# POWER.net
KiCad netlist of a schematic drawn in Altium Designer
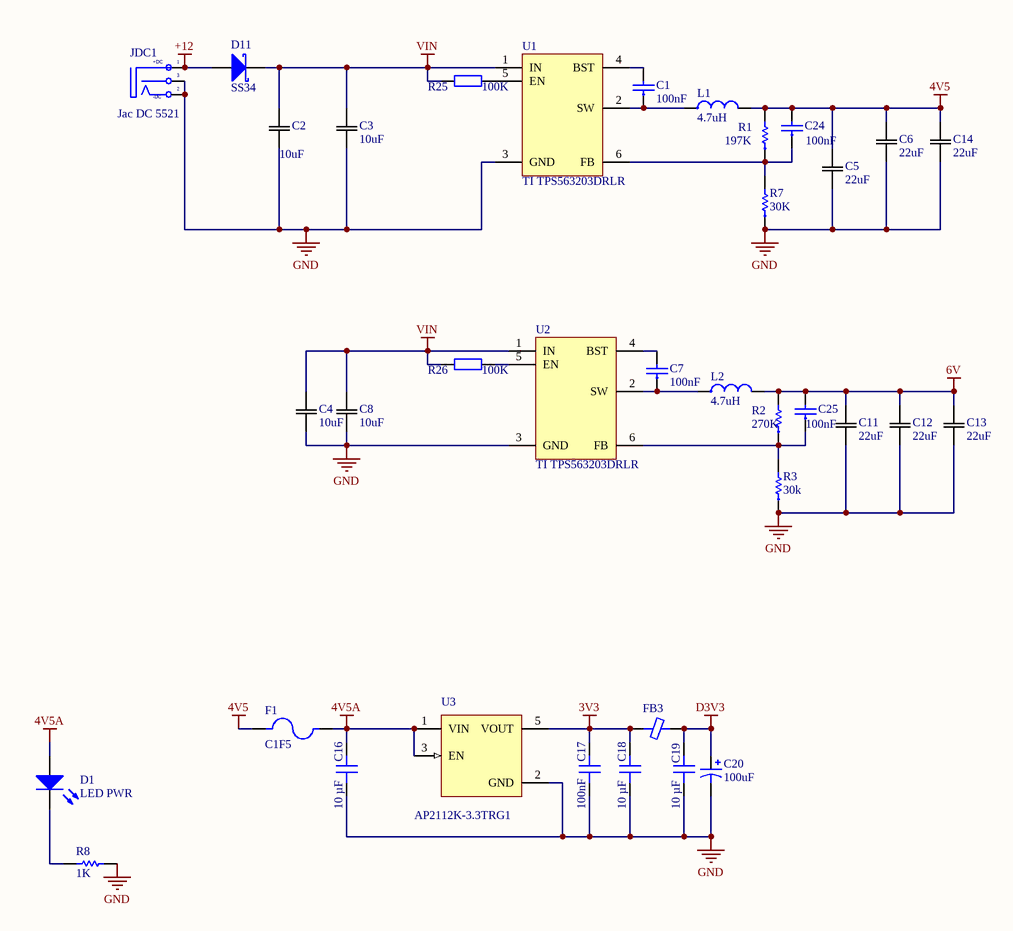
[diagram p0: POWER.SchDoc]

(export (version "E")
  (design (tool "Eeschema 10.0.6"))
  (components
    (comp (ref "C1")
      (value "100nF")
      (footprint "C0603")
      (description "CAP CER 100nF 10% 50V X7R 0603 SMD")
      (libsource (lib "2502-GMQLITE-MAIN") (part "CAPCER0001 100nF 10% 50V X7R 0603 SMD_1"))
    )
    (comp (ref "C2")
      (value "10uF")
      (footprint "CAP_CL10_SAM")
      (description "Description")
      (fields
        (field (name "MANUFACTURER_PART_NUMBER") "CL10A106MQ8NNNC")
        (field (name "COPYRIGHT") "Copyright (C) 2026 Ultra Librarian. All rights reserved.")
      )
      (libsource (lib "CL10A106MQ8NNNC") (part "CL10A106MQ8NNNC"))
    )
    (comp (ref "C3")
      (value "10uF")
      (footprint "CAP_CL10_SAM")
      (description "Description")
      (fields
        (field (name "MANUFACTURER_PART_NUMBER") "CL10A106MQ8NNNC")
        (field (name "COPYRIGHT") "Copyright (C) 2026 Ultra Librarian. All rights reserved.")
      )
      (libsource (lib "CL10A106MQ8NNNC") (part "CL10A106MQ8NNNC"))
    )
    (comp (ref "C4")
      (value "10uF")
      (footprint "CAP_CL10_SAM")
      (description "Description")
      (fields
        (field (name "MANUFACTURER_PART_NUMBER") "CL10A106MQ8NNNC")
        (field (name "COPYRIGHT") "Copyright (C) 2026 Ultra Librarian. All rights reserved.")
      )
      (libsource (lib "CL10A106MQ8NNNC") (part "CL10A106MQ8NNNC"))
    )
    (comp (ref "C5")
      (value "22uF")
      (footprint "G-188_MUR")
      (description "Description")
      (fields
        (field (name "MANUFACTURER_PART_NUMBER") "GRM188R60J226MEA0D")
        (field (name "COPYRIGHT") "Copyright (C) 2026 Ultra Librarian. All rights reserved.")
      )
      (libsource (lib "GRM188R60J226MEA0D") (part "GRM188R60J226MEA0D"))
    )
    (comp (ref "C6")
      (value "22uF")
      (footprint "G-188_MUR")
      (description "Description")
      (fields
        (field (name "MANUFACTURER_PART_NUMBER") "GRM188R60J226MEA0D")
        (field (name "COPYRIGHT") "Copyright (C) 2026 Ultra Librarian. All rights reserved.")
      )
      (libsource (lib "GRM188R60J226MEA0D") (part "GRM188R60J226MEA0D"))
    )
    (comp (ref "C7")
      (value "100nF")
      (footprint "C0603")
      (description "CAP CER 100nF 10% 50V X7R 0603 SMD")
      (libsource (lib "2502-GMQLITE-MAIN") (part "CAPCER0001 100nF 10% 50V X7R 0603 SMD_1"))
    )
    (comp (ref "C8")
      (value "10uF")
      (footprint "CAP_CL10_SAM")
      (description "Description")
      (fields
        (field (name "MANUFACTURER_PART_NUMBER") "CL10A106MQ8NNNC")
        (field (name "COPYRIGHT") "Copyright (C) 2026 Ultra Librarian. All rights reserved.")
      )
      (libsource (lib "CL10A106MQ8NNNC") (part "CL10A106MQ8NNNC"))
    )
    (comp (ref "C11")
      (value "22uF")
      (footprint "G-188_MUR")
      (description "Description")
      (fields
        (field (name "MANUFACTURER_PART_NUMBER") "GRM188R60J226MEA0D")
        (field (name "COPYRIGHT") "Copyright (C) 2026 Ultra Librarian. All rights reserved.")
      )
      (libsource (lib "GRM188R60J226MEA0D") (part "GRM188R60J226MEA0D"))
    )
    (comp (ref "C12")
      (value "22uF")
      (footprint "G-188_MUR")
      (description "Description")
      (fields
        (field (name "MANUFACTURER_PART_NUMBER") "GRM188R60J226MEA0D")
        (field (name "COPYRIGHT") "Copyright (C) 2026 Ultra Librarian. All rights reserved.")
      )
      (libsource (lib "GRM188R60J226MEA0D") (part "GRM188R60J226MEA0D"))
    )
    (comp (ref "C13")
      (value "22uF")
      (footprint "G-188_MUR")
      (description "Description")
      (fields
        (field (name "MANUFACTURER_PART_NUMBER") "GRM188R60J226MEA0D")
        (field (name "COPYRIGHT") "Copyright (C) 2026 Ultra Librarian. All rights reserved.")
      )
      (libsource (lib "GRM188R60J226MEA0D") (part "GRM188R60J226MEA0D"))
    )
    (comp (ref "C14")
      (value "22uF")
      (footprint "G-188_MUR")
      (description "Description")
      (fields
        (field (name "MANUFACTURER_PART_NUMBER") "GRM188R60J226MEA0D")
        (field (name "COPYRIGHT") "Copyright (C) 2026 Ultra Librarian. All rights reserved.")
      )
      (libsource (lib "GRM188R60J226MEA0D") (part "GRM188R60J226MEA0D"))
    )
    (comp (ref "C16")
      (value "10 µF")
      (footprint "C0603")
      (description "CAP0603 X7R 10UF 10% 10V")
      (fields
        (field (name "PART NUMBER") "GMC10X7R106K10NT")
        (field (name "MANUFACTURER") "Cal-Chip Electronics, Inc.")
      )
      (libsource (lib "Celestial Altium Library - altium_library") (part "Capacitor"))
    )
    (comp (ref "C17")
      (value "100nF")
      (footprint "C0603")
      (description "CAP0603 X7R 100nF 10% 10V")
      (fields
        (field (name "PART NUMBER") "GMC10X7R106K10NT")
        (field (name "MANUFACTURER") "Cal-Chip Electronics, Inc.")
      )
      (libsource (lib "Celestial Altium Library - altium_library") (part "Capacitor"))
    )
    (comp (ref "C18")
      (value "10 µF")
      (footprint "C0603")
      (description "CAP0603 X7R 10UF 10% 10V")
      (fields
        (field (name "PART NUMBER") "GMC10X7R106K10NT")
        (field (name "MANUFACTURER") "Cal-Chip Electronics, Inc.")
      )
      (libsource (lib "Celestial Altium Library - altium_library") (part "Capacitor"))
    )
    (comp (ref "C19")
      (value "10 µF")
      (footprint "C0603")
      (description "CAP0603 X7R 10UF 10% 10V")
      (fields
        (field (name "PART NUMBER") "GMC10X7R106K10NT")
        (field (name "MANUFACTURER") "Cal-Chip Electronics, Inc.")
      )
      (libsource (lib "Celestial Altium Library - altium_library") (part "Capacitor"))
    )
    (comp (ref "C20")
      (value "100uF")
      (footprint "CAPACITOR SIZE_D(D6.6)")
      (description "CAP ALUM 100UF 20% \r\n16V SMD")
      (fields (field (name "Comment") "CAP ALUM 100UF 20% 16V SMD"))
      (libsource (lib "capacitor") (part "UWT1C101MCL1GB"))
    )
    (comp (ref "C24")
      (value "100nF")
      (footprint "C0603")
      (description "CAP CER 100nF 10% 50V X7R 0603 SMD")
      (libsource (lib "2502-GMQLITE-MAIN") (part "CAPCER0001 100nF 10% 50V X7R 0603 SMD"))
    )
    (comp (ref "C25")
      (value "100nF")
      (footprint "C0603")
      (description "CAP CER 100nF 10% 50V X7R 0603 SMD")
      (libsource (lib "2502-GMQLITE-MAIN") (part "CAPCER0001 100nF 10% 50V X7R 0603 SMD"))
    )
    (comp (ref "D1")
      (value "LED PWR")
      (footprint "LED0603-R")
      (description "Lite-On LED Red 0603")
      (fields (field (name "Comment") "LED Red"))
      (libsource (lib "diode") (part "LTST-C190KRKT"))
    )
    (comp (ref "D11")
      (value "SS34")
      (footprint "DO-214AC")
      (description "Schottky Diode 40V 3A SMA")
      (libsource (lib "diode") (part "SS34"))
    )
    (comp (ref "F1")
      (value "C1F5")
      (footprint "FUSE C1F5")
      (description "Fuse Chip Fast Acting 5A 125V SMD Solder Pad 1206 3.2 X 1.58 X 0.63mm")
      (fields (field (name "MANUFACTURER") "Bel TRP"))
      (libsource (lib "POWER_PIN_CAMERA") (part "C1F5"))
    )
    (comp (ref "FB3")
      (value "330 Ohms @ 100 MHz")
      (footprint "L0603")
      (description "FERRITE BEAD 330 OHM 0603 1LN")
      (fields
        (field (name "PART NUMBER") "BLM18KG331SH1D")
        (field (name "MANUFACTURER") "Murata Electronics")
      )
      (libsource (lib "Celestial Altium Library - altium_library") (part "Ferrite Chip"))
    )
    (comp (ref "JDC1")
      (value "Jac DC 5521")
      (footprint "DC0")
      (description "Jac DC input")
      (libsource (lib "2502-GMQLITE-MAIN") (part "DCIN"))
    )
    (comp (ref "L1")
      (value "4.7uH")
      (footprint "IND-0420-2R2")
      (description "IND MOI 1W2T 4.7uH 20% 5A 0420 SMD")
      (libsource (lib "2502-GMQLITE-MAIN") (part "INDMOI0016 1W2T 2.2uH 20% 5A 0420 SMD"))
    )
    (comp (ref "L2")
      (value "4.7uH")
      (footprint "IND-0420-2R2")
      (description "IND MOI 1W2T 4.7uH 20% 5A 0420 SMD")
      (libsource (lib "2502-GMQLITE-MAIN") (part "INDMOI0016 1W2T 2.2uH 20% 5A 0420 SMD"))
    )
    (comp (ref "R1")
      (value "197K")
      (footprint "R0603")
      (description "RES CHP 2K7 1% 1/10W 0603 SMD")
      (libsource (lib "2502-GMQLITE-MAIN") (part "RESCHP0195 2K7 1% 0603 SMD"))
    )
    (comp (ref "R2")
      (value "270K")
      (footprint "R0603")
      (description "RES CHP 2K7 1% 1/10W 0603 SMD")
      (libsource (lib "2502-GMQLITE-MAIN") (part "RESCHP0195 2K7 1% 0603 SMD"))
    )
    (comp (ref "R3")
      (value "30k")
      (footprint "R0603")
      (description "RES CHP 2K7 1% 1/10W 0603 SMD")
      (libsource (lib "2502-GMQLITE-MAIN") (part "RESCHP0195 2K7 1% 0603 SMD"))
    )
    (comp (ref "R7")
      (value "30K")
      (footprint "R0603")
      (description "RES CHP 2K7 1% 1/10W 0603 SMD")
      (libsource (lib "2502-GMQLITE-MAIN") (part "RESCHP0195 2K7 1% 0603 SMD"))
    )
    (comp (ref "R8")
      (value "1K")
      (footprint "R0603")
      (description "Res Thick Film 0603 2.2K Ohm 5% 1/10W ±200ppm/°C Molded SMD SMD Paper T/R")
      (fields
        (field (name "MANUFACTURER") "Vishay")
        (field (name "MANUFACTURER PART NUMBER") "CRCW06032K20JNEA")
      )
      (libsource (lib "Stm32_Flyback_Driver_250814_1") (part "Resistor 2.2K"))
    )
    (comp (ref "R25")
      (value "100K")
      (footprint "R0603")
      (description "Yageo RES 100K 5% 1/10W 0603")
      (fields (field (name "Comment") "RES 100K 5% 1/10W 0603"))
      (libsource (lib "resistor") (part "RC0603JR-07100KL"))
    )
    (comp (ref "R26")
      (value "100K")
      (footprint "R0603")
      (description "Yageo RES 100K 5% 1/10W 0603")
      (fields (field (name "Comment") "RES 100K 5% 1/10W 0603"))
      (libsource (lib "resistor") (part "RC0603JR-07100KL"))
    )
    (comp (ref "U1")
      (value "TI TPS563203DRLR")
      (footprint "SOT50P160X60-6N")
      (description "ICS OCV BCK TPS563201 3A SOT23-6 SMD")
      (libsource (lib "2502-GMQLITE-MAIN") (part "ICSOCV0021 BCK TPS563201 3A SOT23-6 SMD"))
    )
    (comp (ref "U2")
      (value "TI TPS563203DRLR")
      (footprint "SOT50P160X60-6N")
      (description "ICS OCV BCK TPS563201 3A SOT23-6 SMD")
      (libsource (lib "2502-GMQLITE-MAIN") (part "ICSOCV0021 BCK TPS563201 3A SOT23-6 SMD"))
    )
    (comp (ref "U3")
      (value "AP2112K-3.3TRG1")
      (footprint "SOT-23-5")
      (description "AP2112 Series 0.6 A 3.3 V Fixed Output SMT LDO Linear Regulator - SOT23-5")
      (fields (field (name "MF") "Diodes Inc."))
      (libsource (lib "hanguyen") (part "AP2112K-3.3TRG1"))
    )
  )
  (nets
    (net (code "1") (name "+12") (class "Default")
      (node (ref "D11") (pin "1") (pinfunction "A_1") (pintype "passive"))
      (node (ref "JDC1") (pin "1") (pinfunction "T_1") (pintype "passive"))
    )
    (net (code "2") (name "3V3") (class "Default")
      (node (ref "C17") (pin "2") (pinfunction "2_2") (pintype "passive"))
      (node (ref "C18") (pin "2") (pinfunction "2_2") (pintype "passive"))
      (node (ref "FB3") (pin "1") (pinfunction "1_1") (pintype "passive"))
      (node (ref "U3") (pin "5") (pinfunction "VOUT_5") (pintype "power_in"))
    )
    (net (code "3") (name "4V5") (class "Default")
      (node (ref "C14") (pin "2") (pinfunction "2_2") (pintype "passive"))
      (node (ref "C24") (pin "2") (pinfunction "2_2") (pintype "passive"))
      (node (ref "C5") (pin "2") (pinfunction "2_2") (pintype "passive"))
      (node (ref "C6") (pin "2") (pinfunction "2_2") (pintype "passive"))
      (node (ref "F1") (pin "1") (pinfunction "1_1") (pintype "passive"))
      (node (ref "L1") (pin "2") (pinfunction "2_2") (pintype "passive"))
      (node (ref "R1") (pin "2") (pinfunction "2_2") (pintype "passive"))
    )
    (net (code "4") (name "4V5A") (class "Default")
      (node (ref "C16") (pin "2") (pinfunction "2_2") (pintype "passive"))
      (node (ref "D1") (pin "1") (pinfunction "A_1") (pintype "passive"))
      (node (ref "F1") (pin "2") (pinfunction "2_2") (pintype "passive"))
      (node (ref "U3") (pin "1") (pinfunction "VIN_1") (pintype "power_in"))
      (node (ref "U3") (pin "3") (pinfunction "EN_3") (pintype "input"))
    )
    (net (code "5") (name "6V") (class "Default")
      (node (ref "C11") (pin "2") (pinfunction "2_2") (pintype "passive"))
      (node (ref "C12") (pin "2") (pinfunction "2_2") (pintype "passive"))
      (node (ref "C13") (pin "2") (pinfunction "2_2") (pintype "passive"))
      (node (ref "C25") (pin "2") (pinfunction "2_2") (pintype "passive"))
      (node (ref "L2") (pin "2") (pinfunction "2_2") (pintype "passive"))
      (node (ref "R2") (pin "2") (pinfunction "2_2") (pintype "passive"))
    )
    (net (code "6") (name "D3V3") (class "Default")
      (node (ref "C19") (pin "2") (pinfunction "2_2") (pintype "passive"))
      (node (ref "C20") (pin "1") (pinfunction "1_1") (pintype "passive"))
      (node (ref "FB3") (pin "2") (pinfunction "2_2") (pintype "passive"))
    )
    (net (code "7") (name "GND") (class "Default")
      (node (ref "C11") (pin "1") (pinfunction "1_1") (pintype "passive"))
      (node (ref "C12") (pin "1") (pinfunction "1_1") (pintype "passive"))
      (node (ref "C13") (pin "1") (pinfunction "1_1") (pintype "passive"))
      (node (ref "C14") (pin "1") (pinfunction "1_1") (pintype "passive"))
      (node (ref "C16") (pin "1") (pinfunction "1_1") (pintype "passive"))
      (node (ref "C17") (pin "1") (pinfunction "1_1") (pintype "passive"))
      (node (ref "C18") (pin "1") (pinfunction "1_1") (pintype "passive"))
      (node (ref "C19") (pin "1") (pinfunction "1_1") (pintype "passive"))
      (node (ref "C2") (pin "1") (pinfunction "1_1") (pintype "passive"))
      (node (ref "C20") (pin "2") (pinfunction "2_2") (pintype "passive"))
      (node (ref "C3") (pin "1") (pinfunction "1_1") (pintype "passive"))
      (node (ref "C4") (pin "1") (pinfunction "1_1") (pintype "passive"))
      (node (ref "C5") (pin "1") (pinfunction "1_1") (pintype "passive"))
      (node (ref "C6") (pin "1") (pinfunction "1_1") (pintype "passive"))
      (node (ref "C8") (pin "1") (pinfunction "1_1") (pintype "passive"))
      (node (ref "JDC1") (pin "2") (pinfunction "TN_2") (pintype "passive"))
      (node (ref "JDC1") (pin "3") (pinfunction "S_3") (pintype "power_in"))
      (node (ref "R3") (pin "1") (pinfunction "1_1") (pintype "passive"))
      (node (ref "R7") (pin "1") (pinfunction "1_1") (pintype "passive"))
      (node (ref "R8") (pin "2") (pinfunction "2_2") (pintype "passive"))
      (node (ref "U1") (pin "3") (pinfunction "GND_3") (pintype "power_in"))
      (node (ref "U2") (pin "3") (pinfunction "GND_3") (pintype "power_in"))
      (node (ref "U3") (pin "2") (pinfunction "GND_2") (pintype "power_in"))
    )
    (net (code "8") (name "Net-(D1-K)") (class "Default")
      (node (ref "D1") (pin "2") (pinfunction "K_2") (pintype "passive"))
      (node (ref "R8") (pin "1") (pinfunction "1_1") (pintype "passive"))
    )
    (net (code "9") (name "Net-(U1-BST)") (class "Default")
      (node (ref "C1") (pin "2") (pinfunction "2_2") (pintype "passive"))
      (node (ref "U1") (pin "4") (pinfunction "BST_4") (pintype "passive"))
    )
    (net (code "10") (name "Net-(U1-EN)") (class "Default")
      (node (ref "R25") (pin "1") (pinfunction "1_1") (pintype "passive"))
      (node (ref "U1") (pin "5") (pinfunction "EN_5") (pintype "passive"))
    )
    (net (code "11") (name "Net-(U1-FB)") (class "Default")
      (node (ref "C24") (pin "1") (pinfunction "1_1") (pintype "passive"))
      (node (ref "R1") (pin "1") (pinfunction "1_1") (pintype "passive"))
      (node (ref "R7") (pin "2") (pinfunction "2_2") (pintype "passive"))
      (node (ref "U1") (pin "6") (pinfunction "FB_6") (pintype "passive"))
    )
    (net (code "12") (name "Net-(U1-SW)") (class "Default")
      (node (ref "C1") (pin "1") (pinfunction "1_1") (pintype "passive"))
      (node (ref "L1") (pin "1") (pinfunction "1_1") (pintype "passive"))
      (node (ref "U1") (pin "2") (pinfunction "SW_2") (pintype "passive"))
    )
    (net (code "13") (name "Net-(U2-BST)") (class "Default")
      (node (ref "C7") (pin "2") (pinfunction "2_2") (pintype "passive"))
      (node (ref "U2") (pin "4") (pinfunction "BST_4") (pintype "passive"))
    )
    (net (code "14") (name "Net-(U2-EN)") (class "Default")
      (node (ref "R26") (pin "1") (pinfunction "1_1") (pintype "passive"))
      (node (ref "U2") (pin "5") (pinfunction "EN_5") (pintype "passive"))
    )
    (net (code "15") (name "Net-(U2-FB)") (class "Default")
      (node (ref "C25") (pin "1") (pinfunction "1_1") (pintype "passive"))
      (node (ref "R2") (pin "1") (pinfunction "1_1") (pintype "passive"))
      (node (ref "R3") (pin "2") (pinfunction "2_2") (pintype "passive"))
      (node (ref "U2") (pin "6") (pinfunction "FB_6") (pintype "passive"))
    )
    (net (code "16") (name "Net-(U2-SW)") (class "Default")
      (node (ref "C7") (pin "1") (pinfunction "1_1") (pintype "passive"))
      (node (ref "L2") (pin "1") (pinfunction "1_1") (pintype "passive"))
      (node (ref "U2") (pin "2") (pinfunction "SW_2") (pintype "passive"))
    )
    (net (code "17") (name "VIN") (class "Default")
      (node (ref "C2") (pin "2") (pinfunction "2_2") (pintype "passive"))
      (node (ref "C3") (pin "2") (pinfunction "2_2") (pintype "passive"))
      (node (ref "C4") (pin "2") (pinfunction "2_2") (pintype "passive"))
      (node (ref "C8") (pin "2") (pinfunction "2_2") (pintype "passive"))
      (node (ref "D11") (pin "2") (pinfunction "K_2") (pintype "passive"))
      (node (ref "R25") (pin "2") (pinfunction "2_2") (pintype "passive"))
      (node (ref "R26") (pin "2") (pinfunction "2_2") (pintype "passive"))
      (node (ref "U1") (pin "1") (pinfunction "IN_1") (pintype "power_in"))
      (node (ref "U2") (pin "1") (pinfunction "IN_1") (pintype "power_in"))
    )
  )
)
